# v1.net
KiCad netlist of a schematic drawn in EAGLE
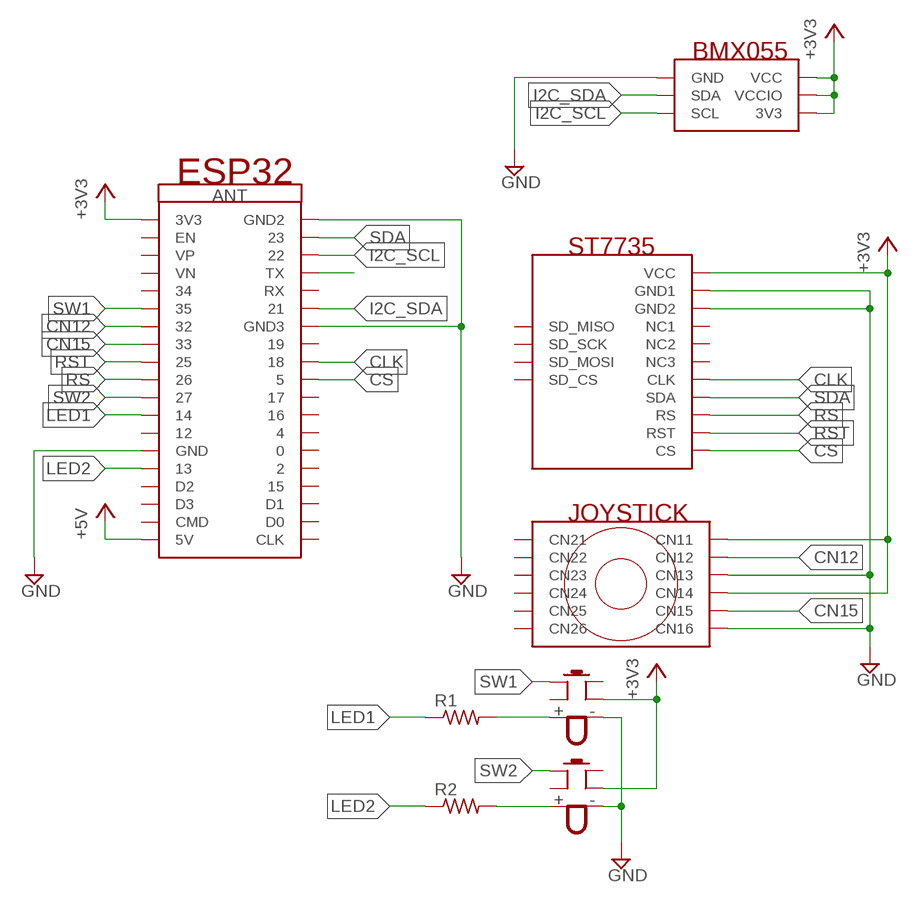
[diagram p0: schematic, sheet 1]

(export (version "E")
  (design (tool "Eeschema 10.0.6"))
  (components
    (comp (ref "R1")
      (value "R-US_0309/12")
      (footprint "eagle-import:0309_12")
      (libsource (lib "eagle-import") (part "R-US_0309/12"))
    )
    (comp (ref "R2")
      (value "R-US_0309/12")
      (footprint "eagle-import:0309_12")
      (libsource (lib "eagle-import") (part "R-US_0309/12"))
    )
    (comp (ref "U$1")
      (value "ST7735")
      (footprint "eagle-import:ST7735")
      (libsource (lib "eagle-import") (part "ST7735"))
    )
    (comp (ref "U$2")
      (value "JOYSTICK")
      (footprint "eagle-import:JOYSTICK")
      (libsource (lib "eagle-import") (part "JOYSTICK"))
    )
    (comp (ref "U$3")
      (value "ESP32")
      (footprint "eagle-import:ESP32")
      (libsource (lib "eagle-import") (part "ESP32"))
    )
    (comp (ref "U$4")
      (value "PUSH_SW_LED")
      (footprint "eagle-import:PUSH_SW_LED")
      (libsource (lib "eagle-import") (part "PUSH_SW_LED"))
    )
    (comp (ref "U$5")
      (value "PUSH_SW_LED")
      (footprint "eagle-import:PUSH_SW_LED")
      (libsource (lib "eagle-import") (part "PUSH_SW_LED"))
    )
    (comp (ref "U$6")
      (value "BMX055")
      (footprint "eagle-import:BMX055")
      (libsource (lib "eagle-import") (part "BMX055"))
    )
  )
  (nets
    (net (code "1") (name "+3V3") (class "Default")
      (node (ref "U$1") (pin "VCC") (pinfunction "VCC_VCC") (pintype "bidirectional"))
      (node (ref "U$2") (pin "CN11") (pinfunction "CN11_CN11") (pintype "bidirectional"))
      (node (ref "U$2") (pin "CN14") (pinfunction "CN14_CN14") (pintype "bidirectional"))
      (node (ref "U$3") (pin "3V3") (pinfunction "3V3_3V3") (pintype "bidirectional"))
      (node (ref "U$4") (pin "P$6") (pinfunction "P4_P$6") (pintype "bidirectional"))
      (node (ref "U$5") (pin "P$6") (pinfunction "P4_P$6") (pintype "bidirectional"))
      (node (ref "U$6") (pin "3V3") (pinfunction "3V3_3V3") (pintype "bidirectional"))
      (node (ref "U$6") (pin "VCC") (pinfunction "VCC_VCC") (pintype "bidirectional"))
      (node (ref "U$6") (pin "VCCIO") (pinfunction "VCCIO_VCCIO") (pintype "bidirectional"))
    )
    (net (code "2") (name "+5V") (class "Default")
      (node (ref "U$3") (pin "5V") (pinfunction "5V_5V") (pintype "bidirectional"))
    )
    (net (code "3") (name "CLK") (class "Default")
      (node (ref "U$1") (pin "CLK") (pinfunction "CLK_CLK") (pintype "bidirectional"))
      (node (ref "U$3") (pin "18") (pinfunction "18_18") (pintype "bidirectional"))
    )
    (net (code "4") (name "CN12") (class "Default")
      (node (ref "U$2") (pin "CN12") (pinfunction "CN12_CN12") (pintype "bidirectional"))
      (node (ref "U$3") (pin "32") (pinfunction "32_32") (pintype "bidirectional"))
    )
    (net (code "5") (name "CN15") (class "Default")
      (node (ref "U$2") (pin "CN15") (pinfunction "CN15_CN15") (pintype "bidirectional"))
      (node (ref "U$3") (pin "33") (pinfunction "33_33") (pintype "bidirectional"))
    )
    (net (code "6") (name "CS") (class "Default")
      (node (ref "U$1") (pin "CS") (pinfunction "CS_CS") (pintype "bidirectional"))
      (node (ref "U$3") (pin "5") (pinfunction "5_5") (pintype "bidirectional"))
    )
    (net (code "7") (name "GND") (class "Default")
      (node (ref "U$1") (pin "GND1") (pinfunction "GND1_GND1") (pintype "bidirectional"))
      (node (ref "U$1") (pin "GND2") (pinfunction "GND2_GND2") (pintype "bidirectional"))
      (node (ref "U$2") (pin "CN13") (pinfunction "CN13_CN13") (pintype "bidirectional"))
      (node (ref "U$2") (pin "CN16") (pinfunction "CN16_CN16") (pintype "bidirectional"))
      (node (ref "U$3") (pin "GND") (pinfunction "GND_GND") (pintype "bidirectional"))
      (node (ref "U$3") (pin "GND2") (pinfunction "GND2_GND2") (pintype "bidirectional"))
      (node (ref "U$3") (pin "GND3") (pinfunction "GND3_GND3") (pintype "bidirectional"))
      (node (ref "U$4") (pin "P$4") (pinfunction "PO_P$4") (pintype "bidirectional"))
      (node (ref "U$5") (pin "P$4") (pinfunction "PO_P$4") (pintype "bidirectional"))
      (node (ref "U$6") (pin "GND") (pinfunction "GND_GND") (pintype "bidirectional"))
    )
    (net (code "8") (name "I2C_SCL") (class "Default")
      (node (ref "U$3") (pin "22") (pinfunction "22_22") (pintype "bidirectional"))
      (node (ref "U$6") (pin "SCL") (pinfunction "SCL_SCL") (pintype "bidirectional"))
    )
    (net (code "9") (name "I2C_SDA") (class "Default")
      (node (ref "U$3") (pin "21") (pinfunction "21_21") (pintype "bidirectional"))
      (node (ref "U$6") (pin "SDA") (pinfunction "SDA_SDA") (pintype "bidirectional"))
    )
    (net (code "10") (name "LED1") (class "Default")
      (node (ref "R1") (pin "1") (pinfunction "1_1") (pintype "passive"))
      (node (ref "U$3") (pin "14") (pinfunction "14_14") (pintype "bidirectional"))
    )
    (net (code "11") (name "LED2") (class "Default")
      (node (ref "R2") (pin "1") (pinfunction "1_1") (pintype "passive"))
      (node (ref "U$3") (pin "13") (pinfunction "13_13") (pintype "bidirectional"))
    )
    (net (code "12") (name "Net-(U$4-PI)") (class "Default")
      (node (ref "R1") (pin "2") (pinfunction "2_2") (pintype "passive"))
      (node (ref "U$4") (pin "P$3") (pinfunction "PI_P$3") (pintype "bidirectional"))
    )
    (net (code "13") (name "Net-(U$5-PI)") (class "Default")
      (node (ref "R2") (pin "2") (pinfunction "2_2") (pintype "passive"))
      (node (ref "U$5") (pin "P$3") (pinfunction "PI_P$3") (pintype "bidirectional"))
    )
    (net (code "14") (name "RS") (class "Default")
      (node (ref "U$1") (pin "RS") (pinfunction "RS_RS") (pintype "bidirectional"))
      (node (ref "U$3") (pin "26") (pinfunction "26_26") (pintype "bidirectional"))
    )
    (net (code "15") (name "RST") (class "Default")
      (node (ref "U$1") (pin "RST") (pinfunction "RST_RST") (pintype "bidirectional"))
      (node (ref "U$3") (pin "25") (pinfunction "25_25") (pintype "bidirectional"))
    )
    (net (code "16") (name "SDA") (class "Default")
      (node (ref "U$1") (pin "SDA") (pinfunction "SDA_SDA") (pintype "bidirectional"))
      (node (ref "U$3") (pin "23") (pinfunction "23_23") (pintype "bidirectional"))
    )
    (net (code "17") (name "SW1") (class "Default")
      (node (ref "U$3") (pin "35") (pinfunction "35_35") (pintype "bidirectional"))
      (node (ref "U$4") (pin "P$1") (pinfunction "P1_P$1") (pintype "bidirectional"))
    )
    (net (code "18") (name "SW2") (class "Default")
      (node (ref "U$3") (pin "27") (pinfunction "27_27") (pintype "bidirectional"))
      (node (ref "U$5") (pin "P$1") (pinfunction "P1_P$1") (pintype "bidirectional"))
    )
    (net (code "19") (name "unconnected-(U$1-PadNC1)") (class "Default")
      (node (ref "U$1") (pin "NC1") (pinfunction "NC1_NC1") (pintype "bidirectional"))
    )
    (net (code "20") (name "unconnected-(U$1-PadNC2)") (class "Default")
      (node (ref "U$1") (pin "NC2") (pinfunction "NC2_NC2") (pintype "bidirectional"))
    )
    (net (code "21") (name "unconnected-(U$1-PadNC3)") (class "Default")
      (node (ref "U$1") (pin "NC3") (pinfunction "NC3_NC3") (pintype "bidirectional"))
    )
    (net (code "22") (name "unconnected-(U$1-PadSD_CS)") (class "Default")
      (node (ref "U$1") (pin "SD_CS") (pinfunction "SD_CS_SD_CS") (pintype "bidirectional"))
    )
    (net (code "23") (name "unconnected-(U$1-PadSD_MISO)") (class "Default")
      (node (ref "U$1") (pin "SD_MISO") (pinfunction "SD_MISO_SD_MISO") (pintype "bidirectional"))
    )
    (net (code "24") (name "unconnected-(U$1-PadSD_MOSI)") (class "Default")
      (node (ref "U$1") (pin "SD_MOSI") (pinfunction "SD_MOSI_SD_MOSI") (pintype "bidirectional"))
    )
    (net (code "25") (name "unconnected-(U$1-PadSD_SCK)") (class "Default")
      (node (ref "U$1") (pin "SD_SCK") (pinfunction "SD_SCK_SD_SCK") (pintype "bidirectional"))
    )
    (net (code "26") (name "unconnected-(U$2-PadCN21)") (class "Default")
      (node (ref "U$2") (pin "CN21") (pinfunction "CN21_CN21") (pintype "bidirectional"))
    )
    (net (code "27") (name "unconnected-(U$2-PadCN22)") (class "Default")
      (node (ref "U$2") (pin "CN22") (pinfunction "CN22_CN22") (pintype "bidirectional"))
    )
    (net (code "28") (name "unconnected-(U$2-PadCN23)") (class "Default")
      (node (ref "U$2") (pin "CN23") (pinfunction "CN23_CN23") (pintype "bidirectional"))
    )
    (net (code "29") (name "unconnected-(U$2-PadCN24)") (class "Default")
      (node (ref "U$2") (pin "CN24") (pinfunction "CN24_CN24") (pintype "bidirectional"))
    )
    (net (code "30") (name "unconnected-(U$2-PadCN25)") (class "Default")
      (node (ref "U$2") (pin "CN25") (pinfunction "CN25_CN25") (pintype "bidirectional"))
    )
    (net (code "31") (name "unconnected-(U$2-PadCN26)") (class "Default")
      (node (ref "U$2") (pin "CN26") (pinfunction "CN26_CN26") (pintype "bidirectional"))
    )
    (net (code "32") (name "unconnected-(U$3-Pad0)") (class "Default")
      (node (ref "U$3") (pin "0") (pinfunction "0_0") (pintype "bidirectional"))
    )
    (net (code "33") (name "unconnected-(U$3-Pad2)") (class "Default")
      (node (ref "U$3") (pin "2") (pinfunction "2_2") (pintype "bidirectional"))
    )
    (net (code "34") (name "unconnected-(U$3-Pad4)") (class "Default")
      (node (ref "U$3") (pin "4") (pinfunction "4_4") (pintype "bidirectional"))
    )
    (net (code "35") (name "unconnected-(U$3-Pad12)") (class "Default")
      (node (ref "U$3") (pin "12") (pinfunction "12_12") (pintype "bidirectional"))
    )
    (net (code "36") (name "unconnected-(U$3-Pad15)") (class "Default")
      (node (ref "U$3") (pin "15") (pinfunction "15_15") (pintype "bidirectional"))
    )
    (net (code "37") (name "unconnected-(U$3-Pad16)") (class "Default")
      (node (ref "U$3") (pin "16") (pinfunction "16_16") (pintype "bidirectional"))
    )
    (net (code "38") (name "unconnected-(U$3-Pad17)") (class "Default")
      (node (ref "U$3") (pin "17") (pinfunction "17_17") (pintype "bidirectional"))
    )
    (net (code "39") (name "unconnected-(U$3-Pad19)") (class "Default")
      (node (ref "U$3") (pin "19") (pinfunction "19_19") (pintype "bidirectional"))
    )
    (net (code "40") (name "unconnected-(U$3-Pad34)") (class "Default")
      (node (ref "U$3") (pin "34") (pinfunction "34_34") (pintype "bidirectional"))
    )
    (net (code "41") (name "unconnected-(U$3-PadCLK)") (class "Default")
      (node (ref "U$3") (pin "CLK") (pinfunction "CLK_CLK") (pintype "bidirectional"))
    )
    (net (code "42") (name "unconnected-(U$3-PadCMD)") (class "Default")
      (node (ref "U$3") (pin "CMD") (pinfunction "CMD_CMD") (pintype "bidirectional"))
    )
    (net (code "43") (name "unconnected-(U$3-PadD0)") (class "Default")
      (node (ref "U$3") (pin "D0") (pinfunction "D0_D0") (pintype "bidirectional"))
    )
    (net (code "44") (name "unconnected-(U$3-PadD1)") (class "Default")
      (node (ref "U$3") (pin "D1") (pinfunction "D1_D1") (pintype "bidirectional"))
    )
    (net (code "45") (name "unconnected-(U$3-PadD2)") (class "Default")
      (node (ref "U$3") (pin "D2") (pinfunction "D2_D2") (pintype "bidirectional"))
    )
    (net (code "46") (name "unconnected-(U$3-PadD3)") (class "Default")
      (node (ref "U$3") (pin "D3") (pinfunction "D3_D3") (pintype "bidirectional"))
    )
    (net (code "47") (name "unconnected-(U$3-PadEN)") (class "Default")
      (node (ref "U$3") (pin "EN") (pinfunction "EN_EN") (pintype "bidirectional"))
    )
    (net (code "48") (name "unconnected-(U$3-PadRX)") (class "Default")
      (node (ref "U$3") (pin "RX") (pinfunction "RX_RX") (pintype "bidirectional"))
    )
    (net (code "49") (name "unconnected-(U$3-PadTX)") (class "Default")
      (node (ref "U$3") (pin "TX") (pinfunction "TX_TX") (pintype "bidirectional"))
    )
    (net (code "50") (name "unconnected-(U$3-PadVN)") (class "Default")
      (node (ref "U$3") (pin "VN") (pinfunction "VN_VN") (pintype "bidirectional"))
    )
    (net (code "51") (name "unconnected-(U$3-PadVP)") (class "Default")
      (node (ref "U$3") (pin "VP") (pinfunction "VP_VP") (pintype "bidirectional"))
    )
    (net (code "52") (name "unconnected-(U$4-P2-PadP$2)") (class "Default")
      (node (ref "U$4") (pin "P$2") (pinfunction "P2_P$2") (pintype "bidirectional"))
    )
    (net (code "53") (name "unconnected-(U$4-P3-PadP$5)") (class "Default")
      (node (ref "U$4") (pin "P$5") (pinfunction "P3_P$5") (pintype "bidirectional"))
    )
    (net (code "54") (name "unconnected-(U$5-P2-PadP$2)") (class "Default")
      (node (ref "U$5") (pin "P$2") (pinfunction "P2_P$2") (pintype "bidirectional"))
    )
    (net (code "55") (name "unconnected-(U$5-P3-PadP$5)") (class "Default")
      (node (ref "U$5") (pin "P$5") (pinfunction "P3_P$5") (pintype "bidirectional"))
    )
  )
)
